# DigitalLabBoard_Switches.net
KiCad netlist of a schematic drawn in Altium Designer
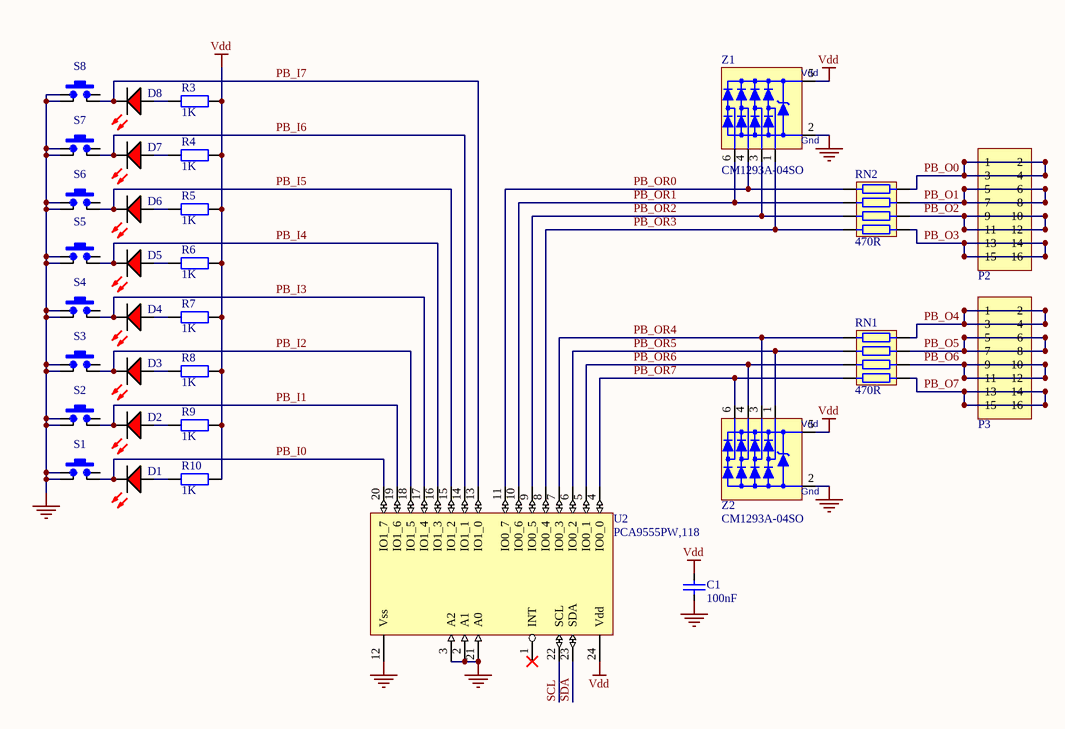
[diagram p0: DigitalLabBoard_Switches.SchDoc]

(export (version "E")
  (design (tool "Eeschema 10.0.6"))
  (components
    (comp (ref "C1")
      (value "100nF")
      (footprint "CCNP1608-0603")
      (description "Capacitor non-polar SMT 0603")
      (fields
        (field (name "MANUFACTURER") "Generic Components")
        (field (name "PUBLISHER") "Altium Hobart Technology Centre")
      )
      (libsource (lib "MyLibrary") (part "Cap_CCNP_0603"))
    )
    (comp (ref "D1")
      (value "LED Red")
      (footprint "LED1608-0603-RED")
      (description "LED 0603 Red")
      (fields (field (name "MANUFACTURER") "Generic Components") (field (name "PUBLISHER") "Altium Limited"))
      (libsource (lib "MySchLib") (part "LED-0603-Red"))
    )
    (comp (ref "D2")
      (value "LED Red")
      (footprint "LED1608-0603-RED")
      (description "LED 0603 Red")
      (fields (field (name "MANUFACTURER") "Generic Components") (field (name "PUBLISHER") "Altium Limited"))
      (libsource (lib "MySchLib") (part "LED-0603-Red"))
    )
    (comp (ref "D3")
      (value "LED Red")
      (footprint "LED1608-0603-RED")
      (description "LED 0603 Red")
      (fields (field (name "MANUFACTURER") "Generic Components") (field (name "PUBLISHER") "Altium Limited"))
      (libsource (lib "MySchLib") (part "LED-0603-Red"))
    )
    (comp (ref "D4")
      (value "LED Red")
      (footprint "LED1608-0603-RED")
      (description "LED 0603 Red")
      (fields (field (name "MANUFACTURER") "Generic Components") (field (name "PUBLISHER") "Altium Limited"))
      (libsource (lib "MySchLib") (part "LED-0603-Red"))
    )
    (comp (ref "D5")
      (value "LED Red")
      (footprint "LED1608-0603-RED")
      (description "LED 0603 Red")
      (fields (field (name "MANUFACTURER") "Generic Components") (field (name "PUBLISHER") "Altium Limited"))
      (libsource (lib "MySchLib") (part "LED-0603-Red"))
    )
    (comp (ref "D6")
      (value "LED Red")
      (footprint "LED1608-0603-RED")
      (description "LED 0603 Red")
      (fields (field (name "MANUFACTURER") "Generic Components") (field (name "PUBLISHER") "Altium Limited"))
      (libsource (lib "MySchLib") (part "LED-0603-Red"))
    )
    (comp (ref "D7")
      (value "LED Red")
      (footprint "LED1608-0603-RED")
      (description "LED 0603 Red")
      (fields (field (name "MANUFACTURER") "Generic Components") (field (name "PUBLISHER") "Altium Limited"))
      (libsource (lib "MySchLib") (part "LED-0603-Red"))
    )
    (comp (ref "D8")
      (value "LED Red")
      (footprint "LED1608-0603-RED")
      (description "LED 0603 Red")
      (fields (field (name "MANUFACTURER") "Generic Components") (field (name "PUBLISHER") "Altium Limited"))
      (libsource (lib "MySchLib") (part "LED-0603-Red"))
    )
    (comp (ref "P2")
      (value "Header 2x8")
      (footprint "HDR2X8S")
      (libsource (lib "MyLibrary") (part "Header 2x8"))
    )
    (comp (ref "P3")
      (value "Header 2x8")
      (footprint "HDR2X8S")
      (libsource (lib "MyLibrary") (part "Header 2x8"))
    )
    (comp (ref "R3")
      (value "1K")
      (footprint "CR1608-0603")
      (description "Resistor SMT 0603")
      (fields
        (field (name "MANUFACTURER") "Generic Components")
        (field (name "PUBLISHER") "Altium Hobart Technology Centre")
      )
      (libsource (lib "MyLibrary") (part "Res_CR0603"))
    )
    (comp (ref "R4")
      (value "1K")
      (footprint "CR1608-0603")
      (description "Resistor SMT 0603")
      (fields
        (field (name "MANUFACTURER") "Generic Components")
        (field (name "PUBLISHER") "Altium Hobart Technology Centre")
      )
      (libsource (lib "MyLibrary") (part "Res_CR0603"))
    )
    (comp (ref "R5")
      (value "1K")
      (footprint "CR1608-0603")
      (description "Resistor SMT 0603")
      (fields
        (field (name "MANUFACTURER") "Generic Components")
        (field (name "PUBLISHER") "Altium Hobart Technology Centre")
      )
      (libsource (lib "MyLibrary") (part "Res_CR0603"))
    )
    (comp (ref "R6")
      (value "1K")
      (footprint "CR1608-0603")
      (description "Resistor SMT 0603")
      (fields
        (field (name "MANUFACTURER") "Generic Components")
        (field (name "PUBLISHER") "Altium Hobart Technology Centre")
      )
      (libsource (lib "MyLibrary") (part "Res_CR0603"))
    )
    (comp (ref "R7")
      (value "1K")
      (footprint "CR1608-0603")
      (description "Resistor SMT 0603")
      (fields
        (field (name "MANUFACTURER") "Generic Components")
        (field (name "PUBLISHER") "Altium Hobart Technology Centre")
      )
      (libsource (lib "MyLibrary") (part "Res_CR0603"))
    )
    (comp (ref "R8")
      (value "1K")
      (footprint "CR1608-0603")
      (description "Resistor SMT 0603")
      (fields
        (field (name "MANUFACTURER") "Generic Components")
        (field (name "PUBLISHER") "Altium Hobart Technology Centre")
      )
      (libsource (lib "MyLibrary") (part "Res_CR0603"))
    )
    (comp (ref "R9")
      (value "1K")
      (footprint "CR1608-0603")
      (description "Resistor SMT 0603")
      (fields
        (field (name "MANUFACTURER") "Generic Components")
        (field (name "PUBLISHER") "Altium Hobart Technology Centre")
      )
      (libsource (lib "MyLibrary") (part "Res_CR0603"))
    )
    (comp (ref "R10")
      (value "1K")
      (footprint "CR1608-0603")
      (description "Resistor SMT 0603")
      (fields
        (field (name "MANUFACTURER") "Generic Components")
        (field (name "PUBLISHER") "Altium Hobart Technology Centre")
      )
      (libsource (lib "MyLibrary") (part "Res_CR0603"))
    )
    (comp (ref "RN1")
      (value "470R")
      (footprint "CR1206-0603_X4_N")
      (description "SMT x4 Resistor Array")
      (libsource (lib "MyLibrary") (part "ResistorNetwork_CR0603x4"))
    )
    (comp (ref "RN2")
      (value "470R")
      (footprint "CR1206-0603_X4_N")
      (description "SMT x4 Resistor Array")
      (libsource (lib "MyLibrary") (part "ResistorNetwork_CR0603x4"))
    )
    (comp (ref "S1")
      (value "~")
      (footprint "SMD-SW-4_5.1x5.1x2.0_M")
      (description "Tactile Switch SPST 5.10mm X 5.10mm\r\n(1.5mm=C318884)\r\n(2.0mm=C318888)\r\n(3.5mm=C318886)")
      (libsource (lib "MySchLib") (part "SW_PB-TS"))
    )
    (comp (ref "S2")
      (value "~")
      (footprint "SMD-SW-4_5.1x5.1x2.0_M")
      (description "Tactile Switch SPST 5.10mm X 5.10mm\r\n(1.5mm=C318884)\r\n(2.0mm=C318888)\r\n(3.5mm=C318886)")
      (libsource (lib "MySchLib") (part "SW_PB-TS"))
    )
    (comp (ref "S3")
      (value "~")
      (footprint "SMD-SW-4_5.1x5.1x2.0_M")
      (description "Tactile Switch SPST 5.10mm X 5.10mm\r\n(1.5mm=C318884)\r\n(2.0mm=C318888)\r\n(3.5mm=C318886)")
      (libsource (lib "MySchLib") (part "SW_PB-TS"))
    )
    (comp (ref "S4")
      (value "~")
      (footprint "SMD-SW-4_5.1x5.1x2.0_M")
      (description "Tactile Switch SPST 5.10mm X 5.10mm\r\n(1.5mm=C318884)\r\n(2.0mm=C318888)\r\n(3.5mm=C318886)")
      (libsource (lib "MySchLib") (part "SW_PB-TS"))
    )
    (comp (ref "S5")
      (value "~")
      (footprint "SMD-SW-4_5.1x5.1x2.0_M")
      (description "Tactile Switch SPST 5.10mm X 5.10mm\r\n(1.5mm=C318884)\r\n(2.0mm=C318888)\r\n(3.5mm=C318886)")
      (libsource (lib "MySchLib") (part "SW_PB-TS"))
    )
    (comp (ref "S6")
      (value "~")
      (footprint "SMD-SW-4_5.1x5.1x2.0_M")
      (description "Tactile Switch SPST 5.10mm X 5.10mm\r\n(1.5mm=C318884)\r\n(2.0mm=C318888)\r\n(3.5mm=C318886)")
      (libsource (lib "MySchLib") (part "SW_PB-TS"))
    )
    (comp (ref "S7")
      (value "~")
      (footprint "SMD-SW-4_5.1x5.1x2.0_M")
      (description "Tactile Switch SPST 5.10mm X 5.10mm\r\n(1.5mm=C318884)\r\n(2.0mm=C318888)\r\n(3.5mm=C318886)")
      (libsource (lib "MySchLib") (part "SW_PB-TS"))
    )
    (comp (ref "S8")
      (value "~")
      (footprint "SMD-SW-4_5.1x5.1x2.0_M")
      (description "Tactile Switch SPST 5.10mm X 5.10mm\r\n(1.5mm=C318884)\r\n(2.0mm=C318888)\r\n(3.5mm=C318886)")
      (libsource (lib "MySchLib") (part "SW_PB-TS"))
    )
    (comp (ref "U2")
      (value "PCA9555PW,118")
      (footprint "TSSOP24_N")
      (description "16-bit I2C I/O Expander (TSSOP24)\r\nPUPs on I/O pins")
      (libsource (lib "MySchLib") (part "PCA9555PW,118"))
    )
    (comp (ref "Z1")
      (value "CM1293A-04SO")
      (footprint "SOT457_N")
      (description "Ultra low capacitance quadruple rail-to-rail ESD protection")
      (libsource (lib "MySchLib") (part "CM1293A-04SO"))
    )
    (comp (ref "Z2")
      (value "CM1293A-04SO")
      (footprint "SOT457_N")
      (description "Ultra low capacitance quadruple rail-to-rail ESD protection")
      (libsource (lib "") (part "CM1293A-04SO_1"))
    )
  )
  (nets
    (net (code "1") (name "/PB_I0") (class "Default")
      (node (ref "D1") (pin "K") (pinfunction "K_K") (pintype "passive"))
      (node (ref "S1") (pin "2") (pinfunction "2_2") (pintype "passive"))
      (node (ref "U2") (pin "20") (pinfunction "IO1_7_20") (pintype "bidirectional"))
    )
    (net (code "2") (name "/PB_I1") (class "Default")
      (node (ref "D2") (pin "K") (pinfunction "K_K") (pintype "passive"))
      (node (ref "S2") (pin "2") (pinfunction "2_2") (pintype "passive"))
      (node (ref "U2") (pin "19") (pinfunction "IO1_6_19") (pintype "bidirectional"))
    )
    (net (code "3") (name "/PB_I2") (class "Default")
      (node (ref "D3") (pin "K") (pinfunction "K_K") (pintype "passive"))
      (node (ref "S3") (pin "2") (pinfunction "2_2") (pintype "passive"))
      (node (ref "U2") (pin "18") (pinfunction "IO1_5_18") (pintype "bidirectional"))
    )
    (net (code "4") (name "/PB_I3") (class "Default")
      (node (ref "D4") (pin "K") (pinfunction "K_K") (pintype "passive"))
      (node (ref "S4") (pin "2") (pinfunction "2_2") (pintype "passive"))
      (node (ref "U2") (pin "17") (pinfunction "IO1_4_17") (pintype "bidirectional"))
    )
    (net (code "5") (name "/PB_I4") (class "Default")
      (node (ref "D5") (pin "K") (pinfunction "K_K") (pintype "passive"))
      (node (ref "S5") (pin "2") (pinfunction "2_2") (pintype "passive"))
      (node (ref "U2") (pin "16") (pinfunction "IO1_3_16") (pintype "bidirectional"))
    )
    (net (code "6") (name "/PB_I5") (class "Default")
      (node (ref "D6") (pin "K") (pinfunction "K_K") (pintype "passive"))
      (node (ref "S6") (pin "2") (pinfunction "2_2") (pintype "passive"))
      (node (ref "U2") (pin "15") (pinfunction "IO1_2_15") (pintype "bidirectional"))
    )
    (net (code "7") (name "/PB_I6") (class "Default")
      (node (ref "D7") (pin "K") (pinfunction "K_K") (pintype "passive"))
      (node (ref "S7") (pin "2") (pinfunction "2_2") (pintype "passive"))
      (node (ref "U2") (pin "14") (pinfunction "IO1_1_14") (pintype "bidirectional"))
    )
    (net (code "8") (name "/PB_I7") (class "Default")
      (node (ref "D8") (pin "K") (pinfunction "K_K") (pintype "passive"))
      (node (ref "S8") (pin "2") (pinfunction "2_2") (pintype "passive"))
      (node (ref "U2") (pin "13") (pinfunction "IO1_0_13") (pintype "bidirectional"))
    )
    (net (code "9") (name "/PB_O0") (class "Default")
      (node (ref "P2") (pin "1") (pinfunction "1_1") (pintype "passive"))
      (node (ref "P2") (pin "2") (pinfunction "2_2") (pintype "passive"))
      (node (ref "P2") (pin "3") (pinfunction "3_3") (pintype "passive"))
      (node (ref "P2") (pin "4") (pinfunction "4_4") (pintype "passive"))
      (node (ref "RN2") (pin "4") (pinfunction "4_4") (pintype "passive"))
    )
    (net (code "10") (name "/PB_O1") (class "Default")
      (node (ref "P2") (pin "5") (pinfunction "5_5") (pintype "passive"))
      (node (ref "P2") (pin "6") (pinfunction "6_6") (pintype "passive"))
      (node (ref "P2") (pin "7") (pinfunction "7_7") (pintype "passive"))
      (node (ref "P2") (pin "8") (pinfunction "8_8") (pintype "passive"))
      (node (ref "RN2") (pin "3") (pinfunction "3_3") (pintype "passive"))
    )
    (net (code "11") (name "/PB_O2") (class "Default")
      (node (ref "P2") (pin "10") (pinfunction "10_10") (pintype "passive"))
      (node (ref "P2") (pin "11") (pinfunction "11_11") (pintype "passive"))
      (node (ref "P2") (pin "12") (pinfunction "12_12") (pintype "passive"))
      (node (ref "P2") (pin "9") (pinfunction "9_9") (pintype "passive"))
      (node (ref "RN2") (pin "2") (pinfunction "2_2") (pintype "passive"))
    )
    (net (code "12") (name "/PB_O3") (class "Default")
      (node (ref "P2") (pin "13") (pinfunction "13_13") (pintype "passive"))
      (node (ref "P2") (pin "14") (pinfunction "14_14") (pintype "passive"))
      (node (ref "P2") (pin "15") (pinfunction "15_15") (pintype "passive"))
      (node (ref "P2") (pin "16") (pinfunction "16_16") (pintype "passive"))
      (node (ref "RN2") (pin "1") (pinfunction "1_1") (pintype "passive"))
    )
    (net (code "13") (name "/PB_O4") (class "Default")
      (node (ref "P3") (pin "1") (pinfunction "1_1") (pintype "passive"))
      (node (ref "P3") (pin "2") (pinfunction "2_2") (pintype "passive"))
      (node (ref "P3") (pin "3") (pinfunction "3_3") (pintype "passive"))
      (node (ref "P3") (pin "4") (pinfunction "4_4") (pintype "passive"))
      (node (ref "RN1") (pin "4") (pinfunction "4_4") (pintype "passive"))
    )
    (net (code "14") (name "/PB_O5") (class "Default")
      (node (ref "P3") (pin "5") (pinfunction "5_5") (pintype "passive"))
      (node (ref "P3") (pin "6") (pinfunction "6_6") (pintype "passive"))
      (node (ref "P3") (pin "7") (pinfunction "7_7") (pintype "passive"))
      (node (ref "P3") (pin "8") (pinfunction "8_8") (pintype "passive"))
      (node (ref "RN1") (pin "3") (pinfunction "3_3") (pintype "passive"))
    )
    (net (code "15") (name "/PB_O6") (class "Default")
      (node (ref "P3") (pin "10") (pinfunction "10_10") (pintype "passive"))
      (node (ref "P3") (pin "11") (pinfunction "11_11") (pintype "passive"))
      (node (ref "P3") (pin "12") (pinfunction "12_12") (pintype "passive"))
      (node (ref "P3") (pin "9") (pinfunction "9_9") (pintype "passive"))
      (node (ref "RN1") (pin "2") (pinfunction "2_2") (pintype "passive"))
    )
    (net (code "16") (name "/PB_O7") (class "Default")
      (node (ref "P3") (pin "13") (pinfunction "13_13") (pintype "passive"))
      (node (ref "P3") (pin "14") (pinfunction "14_14") (pintype "passive"))
      (node (ref "P3") (pin "15") (pinfunction "15_15") (pintype "passive"))
      (node (ref "P3") (pin "16") (pinfunction "16_16") (pintype "passive"))
      (node (ref "RN1") (pin "1") (pinfunction "1_1") (pintype "passive"))
    )
    (net (code "17") (name "/PB_OR0") (class "Default")
      (node (ref "RN2") (pin "5") (pinfunction "5_5") (pintype "passive"))
      (node (ref "U2") (pin "11") (pinfunction "IO0_7_11") (pintype "bidirectional"))
      (node (ref "Z1") (pin "4") (pintype "passive"))
    )
    (net (code "18") (name "/PB_OR1") (class "Default")
      (node (ref "RN2") (pin "6") (pinfunction "6_6") (pintype "passive"))
      (node (ref "U2") (pin "10") (pinfunction "IO0_6_10") (pintype "bidirectional"))
      (node (ref "Z1") (pin "6") (pintype "passive"))
    )
    (net (code "19") (name "/PB_OR2") (class "Default")
      (node (ref "RN2") (pin "7") (pinfunction "7_7") (pintype "passive"))
      (node (ref "U2") (pin "9") (pinfunction "IO0_5_9") (pintype "bidirectional"))
      (node (ref "Z1") (pin "3") (pintype "passive"))
    )
    (net (code "20") (name "/PB_OR3") (class "Default")
      (node (ref "RN2") (pin "8") (pinfunction "8_8") (pintype "passive"))
      (node (ref "U2") (pin "8") (pinfunction "IO0_4_8") (pintype "bidirectional"))
      (node (ref "Z1") (pin "1") (pintype "passive"))
    )
    (net (code "21") (name "/PB_OR4") (class "Default")
      (node (ref "RN1") (pin "5") (pinfunction "5_5") (pintype "passive"))
      (node (ref "U2") (pin "7") (pinfunction "IO0_3_7") (pintype "bidirectional"))
      (node (ref "Z2") (pin "3") (pintype "passive"))
    )
    (net (code "22") (name "/PB_OR5") (class "Default")
      (node (ref "RN1") (pin "6") (pinfunction "6_6") (pintype "passive"))
      (node (ref "U2") (pin "6") (pinfunction "IO0_2_6") (pintype "bidirectional"))
      (node (ref "Z2") (pin "1") (pintype "passive"))
    )
    (net (code "23") (name "/PB_OR6") (class "Default")
      (node (ref "RN1") (pin "7") (pinfunction "7_7") (pintype "passive"))
      (node (ref "U2") (pin "5") (pinfunction "IO0_1_5") (pintype "bidirectional"))
      (node (ref "Z2") (pin "4") (pintype "passive"))
    )
    (net (code "24") (name "/PB_OR7") (class "Default")
      (node (ref "RN1") (pin "8") (pinfunction "8_8") (pintype "passive"))
      (node (ref "U2") (pin "4") (pinfunction "IO0_0_4") (pintype "bidirectional"))
      (node (ref "Z2") (pin "6") (pintype "passive"))
    )
    (net (code "25") (name "/SCL") (class "Default")
      (node (ref "U2") (pin "22") (pinfunction "SCL_22") (pintype "bidirectional"))
    )
    (net (code "26") (name "/SDA") (class "Default")
      (node (ref "U2") (pin "23") (pinfunction "SDA_23") (pintype "bidirectional"))
    )
    (net (code "27") (name "GND") (class "Default")
      (node (ref "C1") (pin "1") (pinfunction "1_1") (pintype "passive"))
      (node (ref "S1") (pin "1") (pinfunction "1_1") (pintype "passive"))
      (node (ref "S1") (pin "1b") (pinfunction "1b_1b") (pintype "passive"))
      (node (ref "S2") (pin "1") (pinfunction "1_1") (pintype "passive"))
      (node (ref "S2") (pin "1b") (pinfunction "1b_1b") (pintype "passive"))
      (node (ref "S3") (pin "1") (pinfunction "1_1") (pintype "passive"))
      (node (ref "S3") (pin "1b") (pinfunction "1b_1b") (pintype "passive"))
      (node (ref "S4") (pin "1") (pinfunction "1_1") (pintype "passive"))
      (node (ref "S4") (pin "1b") (pinfunction "1b_1b") (pintype "passive"))
      (node (ref "S5") (pin "1") (pinfunction "1_1") (pintype "passive"))
      (node (ref "S5") (pin "1b") (pinfunction "1b_1b") (pintype "passive"))
      (node (ref "S6") (pin "1") (pinfunction "1_1") (pintype "passive"))
      (node (ref "S6") (pin "1b") (pinfunction "1b_1b") (pintype "passive"))
      (node (ref "S7") (pin "1") (pinfunction "1_1") (pintype "passive"))
      (node (ref "S7") (pin "1b") (pinfunction "1b_1b") (pintype "passive"))
      (node (ref "S8") (pin "1") (pinfunction "1_1") (pintype "passive"))
      (node (ref "S8") (pin "1b") (pinfunction "1b_1b") (pintype "passive"))
      (node (ref "U2") (pin "12") (pinfunction "Vss_12") (pintype "power_in"))
      (node (ref "U2") (pin "2") (pinfunction "A1_2") (pintype "input"))
      (node (ref "U2") (pin "21") (pinfunction "A0_21") (pintype "input"))
      (node (ref "U2") (pin "3") (pinfunction "A2_3") (pintype "input"))
      (node (ref "Z1") (pin "2") (pinfunction "Vn_2") (pintype "passive"))
      (node (ref "Z2") (pin "2") (pinfunction "Vn_2") (pintype "passive"))
    )
    (net (code "28") (name "Net-(D1-PadA)") (class "Default")
      (node (ref "D1") (pin "A") (pinfunction "A_A") (pintype "passive"))
      (node (ref "R10") (pin "1") (pinfunction "1_1") (pintype "passive"))
    )
    (net (code "29") (name "Net-(D2-PadA)") (class "Default")
      (node (ref "D2") (pin "A") (pinfunction "A_A") (pintype "passive"))
      (node (ref "R9") (pin "1") (pinfunction "1_1") (pintype "passive"))
    )
    (net (code "30") (name "Net-(D3-PadA)") (class "Default")
      (node (ref "D3") (pin "A") (pinfunction "A_A") (pintype "passive"))
      (node (ref "R8") (pin "1") (pinfunction "1_1") (pintype "passive"))
    )
    (net (code "31") (name "Net-(D4-PadA)") (class "Default")
      (node (ref "D4") (pin "A") (pinfunction "A_A") (pintype "passive"))
      (node (ref "R7") (pin "1") (pinfunction "1_1") (pintype "passive"))
    )
    (net (code "32") (name "Net-(D5-PadA)") (class "Default")
      (node (ref "D5") (pin "A") (pinfunction "A_A") (pintype "passive"))
      (node (ref "R6") (pin "1") (pinfunction "1_1") (pintype "passive"))
    )
    (net (code "33") (name "Net-(D6-PadA)") (class "Default")
      (node (ref "D6") (pin "A") (pinfunction "A_A") (pintype "passive"))
      (node (ref "R5") (pin "1") (pinfunction "1_1") (pintype "passive"))
    )
    (net (code "34") (name "Net-(D7-PadA)") (class "Default")
      (node (ref "D7") (pin "A") (pinfunction "A_A") (pintype "passive"))
      (node (ref "R4") (pin "1") (pinfunction "1_1") (pintype "passive"))
    )
    (net (code "35") (name "Net-(D8-PadA)") (class "Default")
      (node (ref "D8") (pin "A") (pinfunction "A_A") (pintype "passive"))
      (node (ref "R3") (pin "1") (pinfunction "1_1") (pintype "passive"))
    )
    (net (code "36") (name "Vdd") (class "Default")
      (node (ref "C1") (pin "2") (pinfunction "2_2") (pintype "passive"))
      (node (ref "R10") (pin "2") (pinfunction "2_2") (pintype "passive"))
      (node (ref "R3") (pin "2") (pinfunction "2_2") (pintype "passive"))
      (node (ref "R4") (pin "2") (pinfunction "2_2") (pintype "passive"))
      (node (ref "R5") (pin "2") (pinfunction "2_2") (pintype "passive"))
      (node (ref "R6") (pin "2") (pinfunction "2_2") (pintype "passive"))
      (node (ref "R7") (pin "2") (pinfunction "2_2") (pintype "passive"))
      (node (ref "R8") (pin "2") (pinfunction "2_2") (pintype "passive"))
      (node (ref "R9") (pin "2") (pinfunction "2_2") (pintype "passive"))
      (node (ref "U2") (pin "24") (pinfunction "Vdd_24") (pintype "power_in"))
      (node (ref "Z1") (pin "5") (pinfunction "Vp_5") (pintype "passive"))
      (node (ref "Z2") (pin "5") (pinfunction "Vp_5") (pintype "passive"))
    )
    (net (code "37") (name "unconnected-(S1-Pad2b)") (class "Default")
      (node (ref "S1") (pin "2b") (pinfunction "2b_2b") (pintype "passive"))
    )
    (net (code "38") (name "unconnected-(S2-Pad2b)") (class "Default")
      (node (ref "S2") (pin "2b") (pinfunction "2b_2b") (pintype "passive"))
    )
    (net (code "39") (name "unconnected-(S3-Pad2b)") (class "Default")
      (node (ref "S3") (pin "2b") (pinfunction "2b_2b") (pintype "passive"))
    )
    (net (code "40") (name "unconnected-(S4-Pad2b)") (class "Default")
      (node (ref "S4") (pin "2b") (pinfunction "2b_2b") (pintype "passive"))
    )
    (net (code "41") (name "unconnected-(S5-Pad2b)") (class "Default")
      (node (ref "S5") (pin "2b") (pinfunction "2b_2b") (pintype "passive"))
    )
    (net (code "42") (name "unconnected-(S6-Pad2b)") (class "Default")
      (node (ref "S6") (pin "2b") (pinfunction "2b_2b") (pintype "passive"))
    )
    (net (code "43") (name "unconnected-(S7-Pad2b)") (class "Default")
      (node (ref "S7") (pin "2b") (pinfunction "2b_2b") (pintype "passive"))
    )
    (net (code "44") (name "unconnected-(S8-Pad2b)") (class "Default")
      (node (ref "S8") (pin "2b") (pinfunction "2b_2b") (pintype "passive"))
    )
    (net (code "45") (name "unconnected-(U2-INT-Pad1)") (class "Default")
      (node (ref "U2") (pin "1") (pinfunction "INT_1") (pintype "open_collector+no_connect"))
    )
  )
)
